# 5V_DIMM_VCCO.net
KiCad netlist of a schematic drawn in Altium Designer
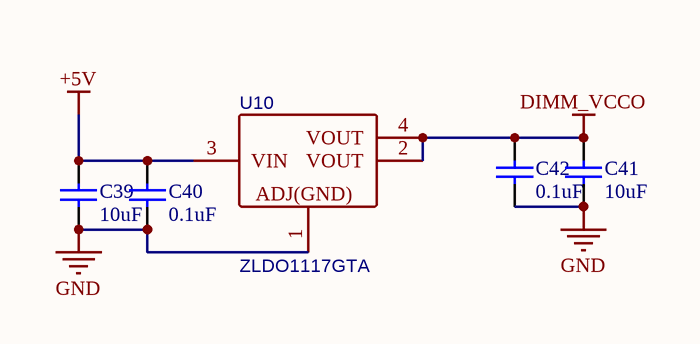
[diagram p0: 5V_DIMM_VCCO.SchDoc]

(export (version "E")
  (design (tool "Eeschema 10.0.6"))
  (components
    (comp (ref "C39")
      (value "10uF")
      (footprint "C1210")
      (description "Capacitor (Semiconductor SIM Model)")
      (fields (field (name "Comment") "Cap Semi") (field (name "PUBLISHER") "Altium Limited"))
      (libsource (lib "Miscellaneous Devices") (part "Cap Semi"))
    )
    (comp (ref "C40")
      (value "0.1uF")
      (footprint "C1210")
      (description "Capacitor (Semiconductor SIM Model)")
      (fields (field (name "Comment") "Cap Semi") (field (name "PUBLISHER") "Altium Limited"))
      (libsource (lib "Miscellaneous Devices") (part "Cap Semi"))
    )
    (comp (ref "C41")
      (value "10uF")
      (footprint "C1210")
      (description "Capacitor (Semiconductor SIM Model)")
      (fields (field (name "Comment") "Cap Semi") (field (name "PUBLISHER") "Altium Limited"))
      (libsource (lib "Miscellaneous Devices") (part "Cap Semi"))
    )
    (comp (ref "C42")
      (value "0.1uF")
      (footprint "C1210")
      (description "Capacitor (Semiconductor SIM Model)")
      (fields (field (name "Comment") "Cap Semi") (field (name "PUBLISHER") "Altium Limited"))
      (libsource (lib "Miscellaneous Devices") (part "Cap Semi"))
    )
    (comp (ref "U10")
      (value "ZLDO1117GTA")
      (footprint "SOT-223-4_L6.5-W3.5-P2.30-LS7.0-BR")
      (fields (field (name "BOM_SUPPLIER PART") "C443633") (field (name "CONTRIBUTOR") "LCSC"))
      (libsource (lib "power_chip") (part "ZLDO1117GTA"))
    )
  )
  (nets
    (net (code "1") (name "+5V") (class "Default")
      (node (ref "C39") (pin "1") (pinfunction "1_1") (pintype "passive"))
      (node (ref "C40") (pin "1") (pinfunction "1_1") (pintype "passive"))
      (node (ref "U10") (pin "3") (pinfunction "VIN_3") (pintype "passive"))
    )
    (net (code "2") (name "DIMM_VCCO") (class "Default")
      (node (ref "C41") (pin "1") (pinfunction "1_1") (pintype "passive"))
      (node (ref "C42") (pin "1") (pinfunction "1_1") (pintype "passive"))
      (node (ref "U10") (pin "2") (pinfunction "VOUT_2") (pintype "passive"))
      (node (ref "U10") (pin "4") (pinfunction "VOUT_4") (pintype "passive"))
    )
    (net (code "3") (name "GND") (class "Default")
      (node (ref "C39") (pin "2") (pinfunction "2_2") (pintype "passive"))
      (node (ref "C40") (pin "2") (pinfunction "2_2") (pintype "passive"))
      (node (ref "C41") (pin "2") (pinfunction "2_2") (pintype "passive"))
      (node (ref "C42") (pin "2") (pinfunction "2_2") (pintype "passive"))
      (node (ref "U10") (pin "1") (pinfunction "ADJ(GND)_1") (pintype "passive"))
    )
  )
)
